# blinkyBoard.net
KiCad netlist of a schematic drawn in EAGLE
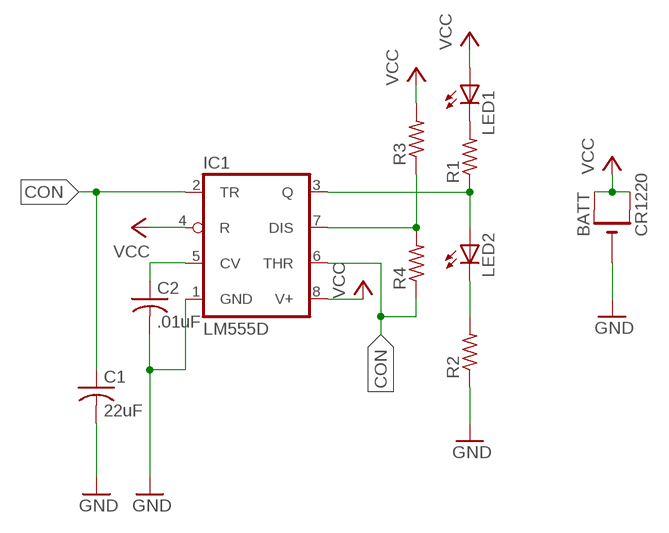
[diagram p0: schematic, sheet 1]

(export (version "E")
  (design (tool "Eeschema 10.0.6"))
  (components
    (comp (ref "BATT")
      (value "CR1220")
      (footprint "eagle-import:CR1220-SMD")
      (fields (field (name "MF") "HARWIN") (field (name "MPN") "S8201-46R"))
      (libsource (lib "eagle-import") (part "CR1220SMT"))
    )
    (comp (ref "C1")
      (value "22uF")
      (footprint "eagle-import:C0805")
      (fields (field (name "MF") "MURATA") (field (name "MPN") "GRM21BR60J226ME39L"))
      (libsource (lib "eagle-import") (part "C-USC0805"))
    )
    (comp (ref "C2")
      (value ".01uF")
      (footprint "eagle-import:C0805")
      (fields (field (name "MF") "KEMET") (field (name "MPN") "C0805C103K5RACTU"))
      (libsource (lib "eagle-import") (part "C-USC0805"))
    )
    (comp (ref "IC1")
      (value "LM555D")
      (footprint "eagle-import:SO08")
      (fields (field (name "MF") "TEXAS INSTRUMENTS") (field (name "MPN") "TLC555CD"))
      (libsource (lib "eagle-import") (part "555DLM"))
    )
    (comp (ref "LED1")
      (value "LEDCHIP-LED0805")
      (footprint "eagle-import:CHIP-LED0805")
      (fields (field (name "MF") "LUMEX") (field (name "MPN") "SML-LX0805SGC-TR"))
      (libsource (lib "eagle-import") (part "LEDCHIP-LED0805"))
    )
    (comp (ref "LED2")
      (value "LEDCHIP-LED0805")
      (footprint "eagle-import:CHIP-LED0805")
      (fields (field (name "MF") "LUMEX") (field (name "MPN") "SML-LX0805SGC-TR"))
      (libsource (lib "eagle-import") (part "LEDCHIP-LED0805"))
    )
    (comp (ref "R1")
      (value "R-US_R0805")
      (footprint "eagle-import:R0805")
      (fields (field (name "MF") "VISHAY") (field (name "MPN") "CRCW0805100RJNEA"))
      (libsource (lib "eagle-import") (part "R-US_R0805"))
    )
    (comp (ref "R2")
      (value "R-US_R0805")
      (footprint "eagle-import:R0805")
      (fields (field (name "MF") "VISHAY") (field (name "MPN") "CRCW0805100RJNEA"))
      (libsource (lib "eagle-import") (part "R-US_R0805"))
    )
    (comp (ref "R3")
      (value "R-US_R0805")
      (footprint "eagle-import:R0805")
      (fields (field (name "MF") "VISHAY") (field (name "MPN") "CRCW0805100RJNEA"))
      (libsource (lib "eagle-import") (part "R-US_R0805"))
    )
    (comp (ref "R4")
      (value "R-US_R0805")
      (footprint "eagle-import:R0805")
      (fields (field (name "MF") "VISHAY") (field (name "MPN") "CRCW0805100RJNEA"))
      (libsource (lib "eagle-import") (part "R-US_R0805"))
    )
  )
  (nets
    (net (code "1") (name "CON") (class "Default")
      (node (ref "C1") (pin "1") (pinfunction "1_1") (pintype "passive"))
      (node (ref "IC1") (pin "2") (pinfunction "TR_2") (pintype "input"))
      (node (ref "IC1") (pin "6") (pinfunction "THR_6") (pintype "input"))
      (node (ref "R4") (pin "1") (pinfunction "1_1") (pintype "passive"))
    )
    (net (code "2") (name "GND") (class "Default")
      (node (ref "BATT") (pin "-") (pinfunction "-_-") (pintype "passive"))
      (node (ref "C1") (pin "2") (pinfunction "2_2") (pintype "passive"))
      (node (ref "C2") (pin "2") (pinfunction "2_2") (pintype "passive"))
      (node (ref "IC1") (pin "1") (pinfunction "GND_1") (pintype "power_in"))
      (node (ref "R2") (pin "1") (pinfunction "1_1") (pintype "passive"))
    )
    (net (code "3") (name "Net-(IC1-CV)") (class "Default")
      (node (ref "C2") (pin "1") (pinfunction "1_1") (pintype "passive"))
      (node (ref "IC1") (pin "5") (pinfunction "CV_5") (pintype "input"))
    )
    (net (code "4") (name "Net-(IC1-DIS)") (class "Default")
      (node (ref "IC1") (pin "7") (pinfunction "DIS_7") (pintype "input"))
      (node (ref "R3") (pin "1") (pinfunction "1_1") (pintype "passive"))
      (node (ref "R4") (pin "2") (pinfunction "2_2") (pintype "passive"))
    )
    (net (code "5") (name "Net-(IC1-Q)") (class "Default")
      (node (ref "IC1") (pin "3") (pinfunction "Q_3") (pintype "output"))
      (node (ref "LED2") (pin "A") (pinfunction "A_A") (pintype "passive"))
      (node (ref "R1") (pin "1") (pinfunction "1_1") (pintype "passive"))
    )
    (net (code "6") (name "Net-(LED1-PadC)") (class "Default")
      (node (ref "LED1") (pin "C") (pinfunction "C_C") (pintype "passive"))
      (node (ref "R1") (pin "2") (pinfunction "2_2") (pintype "passive"))
    )
    (net (code "7") (name "Net-(LED2-PadC)") (class "Default")
      (node (ref "LED2") (pin "C") (pinfunction "C_C") (pintype "passive"))
      (node (ref "R2") (pin "2") (pinfunction "2_2") (pintype "passive"))
    )
    (net (code "8") (name "VCC") (class "Default")
      (node (ref "BATT") (pin "+$1") (pinfunction "+_+$1") (pintype "passive"))
      (node (ref "BATT") (pin "+$2") (pinfunction "+1_+$2") (pintype "passive"))
      (node (ref "IC1") (pin "4") (pinfunction "R_4") (pintype "input"))
      (node (ref "IC1") (pin "8") (pinfunction "V+_8") (pintype "power_in"))
      (node (ref "LED1") (pin "A") (pinfunction "A_A") (pintype "passive"))
      (node (ref "R3") (pin "2") (pinfunction "2_2") (pintype "passive"))
    )
  )
)
